# tornado-Backplane.net
KiCad netlist of a schematic drawn in EAGLE
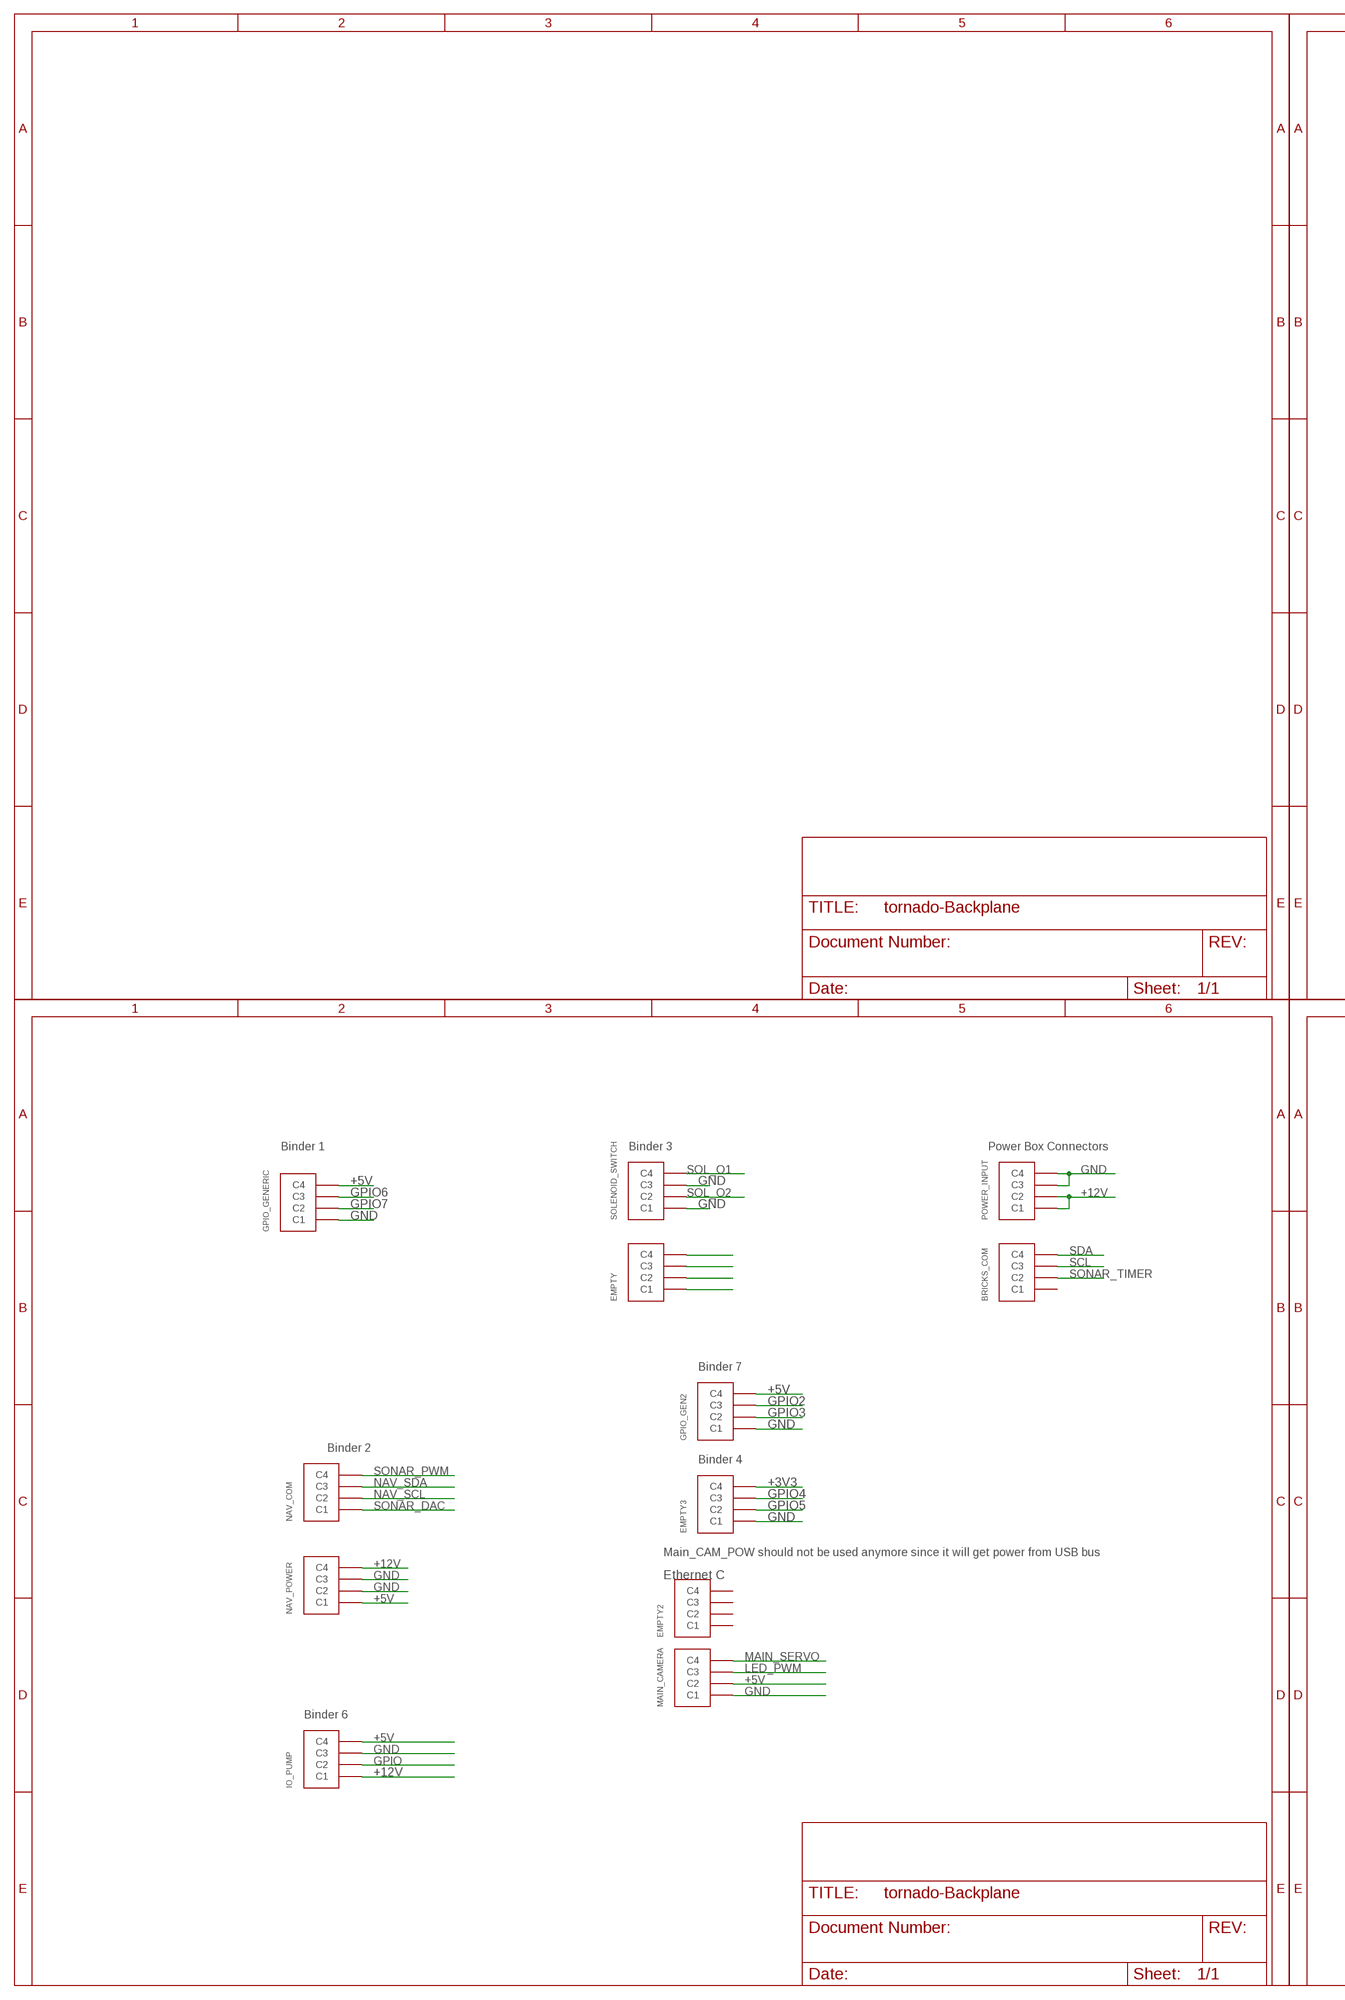
[diagram p0: schematic, sheet 1, part 1 of 2]
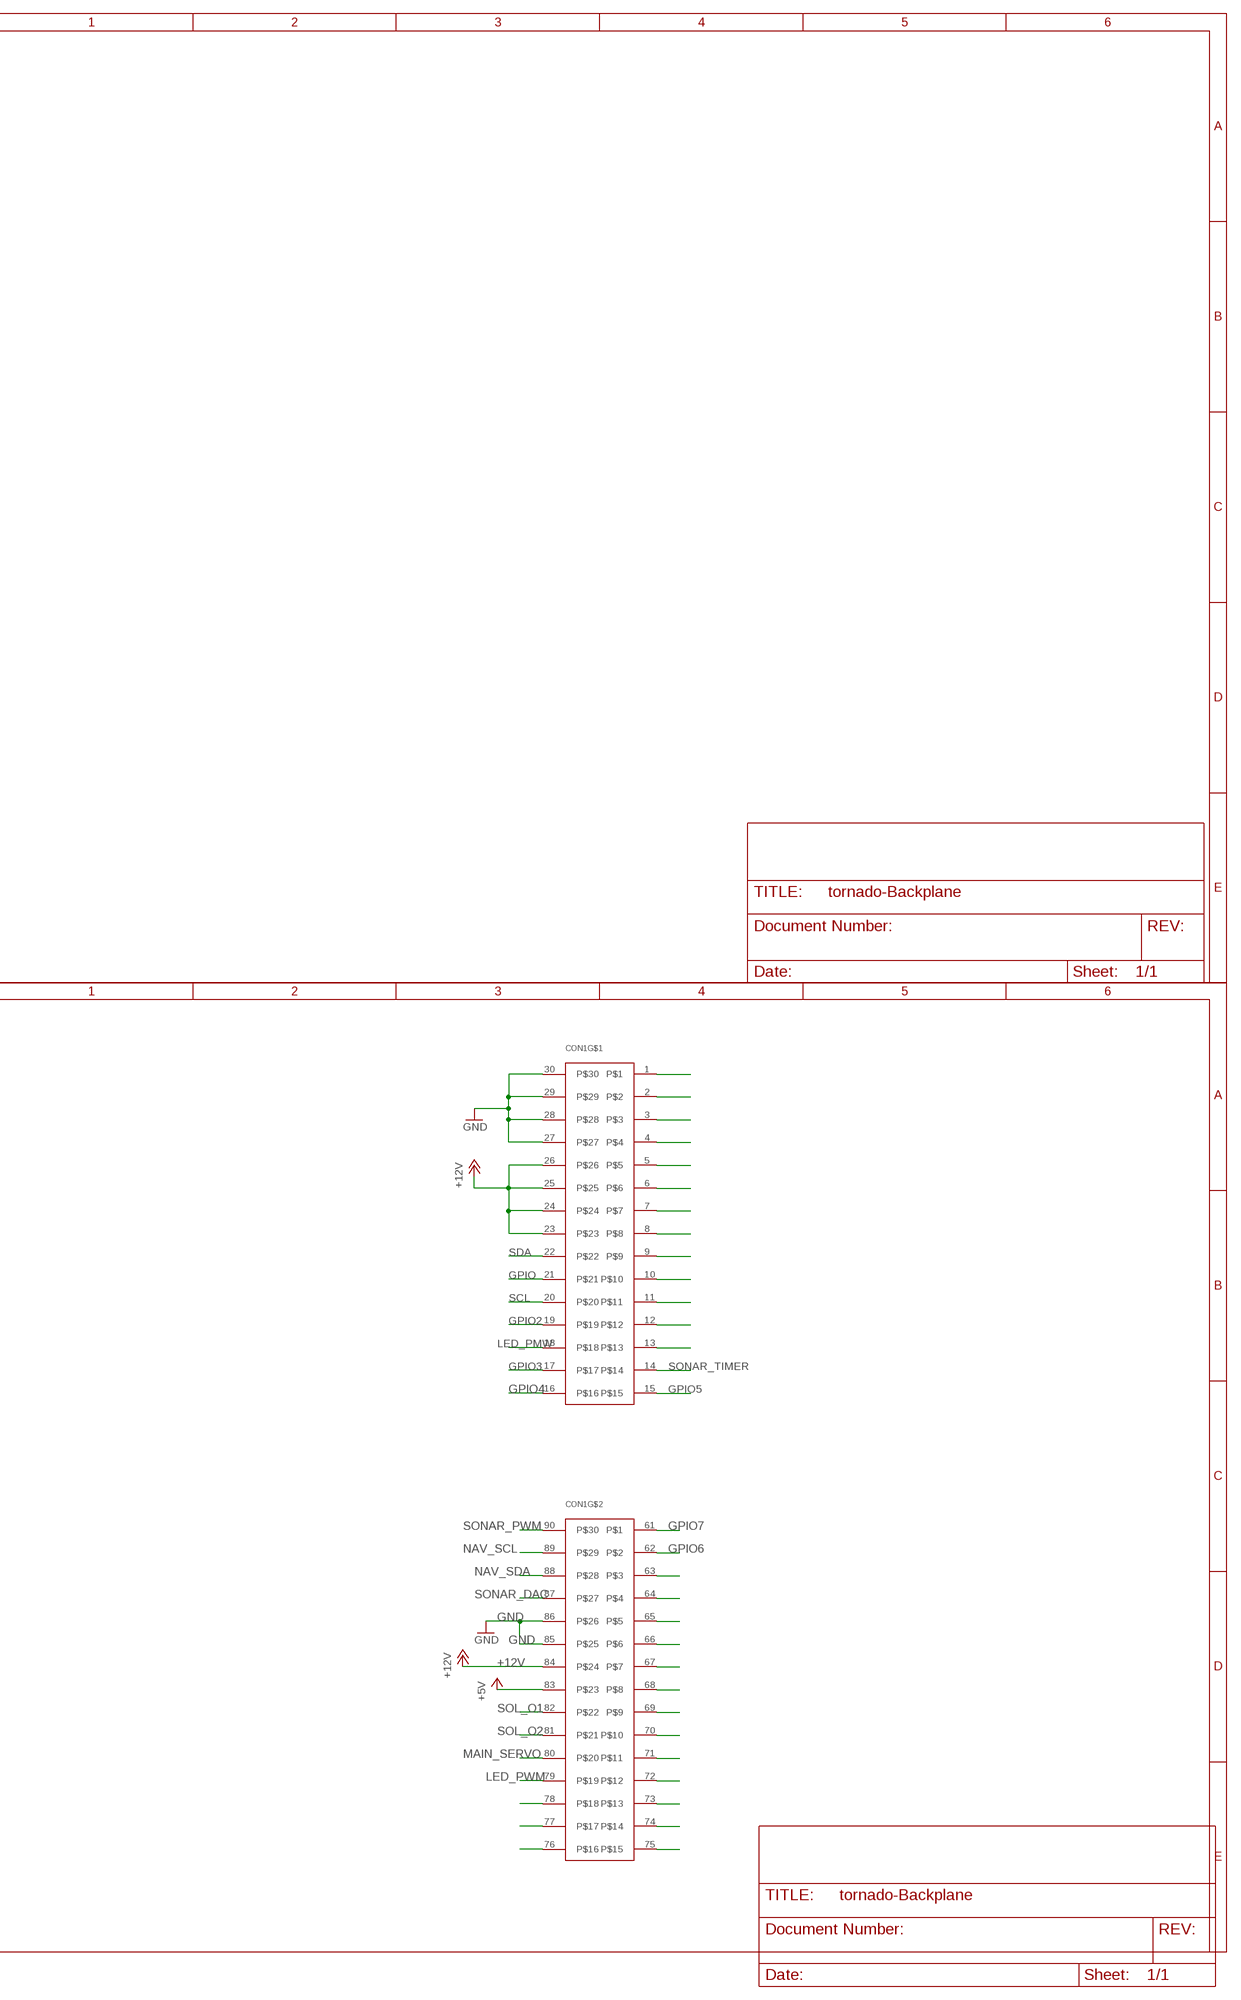
[diagram p1: schematic, sheet 1, part 2 of 2]

(export (version "E")
  (design (tool "Eeschema 10.0.6"))
  (components
    (comp (ref "BRICKS_COM")
      (value "MICRO-FIT-4-SMD-PART")
      (footprint "eagle-import:MICRO-FIT-4-SMD")
      (libsource (lib "eagle-import") (part "MICRO-FIT-4-SMD-PART"))
    )
    (comp (ref "CON1")
      (value "ROV_SHIELD_V2")
      (footprint "eagle-import:ROV_SHIELD_V2")
      (libsource (lib "eagle-import") (part "ROV_SHIELD_V2"))
    )
    (comp (ref "EMPTY")
      (value "MICRO-FIT-4-SMD-PART")
      (footprint "eagle-import:MICRO-FIT-4-SMD")
      (libsource (lib "eagle-import") (part "MICRO-FIT-4-SMD-PART"))
    )
    (comp (ref "EMPTY2")
      (value "MICRO-FIT-4-SMD-PART")
      (footprint "eagle-import:MICRO-FIT-4-SMD")
      (libsource (lib "eagle-import") (part "MICRO-FIT-4-SMD-PART"))
    )
    (comp (ref "EMPTY3")
      (value "MICRO-FIT-4-SMD-PART")
      (footprint "eagle-import:MICRO-FIT-4-SMD")
      (libsource (lib "eagle-import") (part "MICRO-FIT-4-SMD-PART"))
    )
    (comp (ref "GPIO_GEN2")
      (value "MICRO-FIT-4-SMD-PART")
      (footprint "eagle-import:MICRO-FIT-4-SMD")
      (libsource (lib "eagle-import") (part "MICRO-FIT-4-SMD-PART"))
    )
    (comp (ref "GPIO_GENERIC")
      (value "MICRO-FIT-4-SMD-PART")
      (footprint "eagle-import:MICRO-FIT-4-SMD")
      (libsource (lib "eagle-import") (part "MICRO-FIT-4-SMD-PART"))
    )
    (comp (ref "IO_PUMP")
      (value "MICRO-FIT-4-SMD-PART")
      (footprint "eagle-import:MICRO-FIT-4-SMD")
      (libsource (lib "eagle-import") (part "MICRO-FIT-4-SMD-PART"))
    )
    (comp (ref "MAIN_CAMERA")
      (value "MICRO-FIT-4-SMD-PART")
      (footprint "eagle-import:MICRO-FIT-4-SMD")
      (libsource (lib "eagle-import") (part "MICRO-FIT-4-SMD-PART"))
    )
    (comp (ref "NAV_COM")
      (value "MICRO-FIT-4-SMD-PART")
      (footprint "eagle-import:MICRO-FIT-4-SMD")
      (libsource (lib "eagle-import") (part "MICRO-FIT-4-SMD-PART"))
    )
    (comp (ref "NAV_POWER")
      (value "MICRO-FIT-4-SMD-PART")
      (footprint "eagle-import:MICRO-FIT-4-SMD")
      (libsource (lib "eagle-import") (part "MICRO-FIT-4-SMD-PART"))
    )
    (comp (ref "POWER_INPUT")
      (value "MICRO-FIT-4-SMD-PART")
      (footprint "eagle-import:MICRO-FIT-4-SMD")
      (libsource (lib "eagle-import") (part "MICRO-FIT-4-SMD-PART"))
    )
    (comp (ref "SOLENOID_SWITCH")
      (value "MICRO-FIT-4-SMD-PART")
      (footprint "eagle-import:MICRO-FIT-4-SMD")
      (libsource (lib "eagle-import") (part "MICRO-FIT-4-SMD-PART"))
    )
  )
  (nets
    (net (code "1") (name "+5V") (class "Default")
      (node (ref "CON1") (pin "83") (pinfunction "P$23_83") (pintype "bidirectional"))
      (node (ref "GPIO_GEN2") (pin "C4") (pinfunction "C4_C4") (pintype "bidirectional"))
      (node (ref "GPIO_GENERIC") (pin "C4") (pinfunction "C4_C4") (pintype "bidirectional"))
      (node (ref "IO_PUMP") (pin "C4") (pinfunction "C4_C4") (pintype "bidirectional"))
      (node (ref "MAIN_CAMERA") (pin "C2") (pinfunction "C2_C2") (pintype "bidirectional"))
      (node (ref "NAV_POWER") (pin "C1") (pinfunction "C1_C1") (pintype "bidirectional"))
    )
    (net (code "2") (name "+12V") (class "Default")
      (node (ref "CON1") (pin "23") (pinfunction "P$23_23") (pintype "bidirectional"))
      (node (ref "CON1") (pin "24") (pinfunction "P$24_24") (pintype "bidirectional"))
      (node (ref "CON1") (pin "25") (pinfunction "P$25_25") (pintype "bidirectional"))
      (node (ref "CON1") (pin "26") (pinfunction "P$26_26") (pintype "bidirectional"))
      (node (ref "CON1") (pin "84") (pinfunction "P$24_84") (pintype "bidirectional"))
      (node (ref "IO_PUMP") (pin "C1") (pinfunction "C1_C1") (pintype "bidirectional"))
      (node (ref "NAV_POWER") (pin "C4") (pinfunction "C4_C4") (pintype "bidirectional"))
      (node (ref "POWER_INPUT") (pin "C1") (pinfunction "C1_C1") (pintype "bidirectional"))
      (node (ref "POWER_INPUT") (pin "C2") (pinfunction "C2_C2") (pintype "bidirectional"))
    )
    (net (code "3") (name "/+3V3") (class "Default")
      (node (ref "EMPTY3") (pin "C4") (pinfunction "C4_C4") (pintype "bidirectional"))
    )
    (net (code "4") (name "/GPIO") (class "Default")
      (node (ref "CON1") (pin "21") (pinfunction "P$21_21") (pintype "bidirectional"))
      (node (ref "IO_PUMP") (pin "C2") (pinfunction "C2_C2") (pintype "bidirectional"))
    )
    (net (code "5") (name "/GPIO2") (class "Default")
      (node (ref "CON1") (pin "19") (pinfunction "P$19_19") (pintype "bidirectional"))
      (node (ref "GPIO_GEN2") (pin "C3") (pinfunction "C3_C3") (pintype "bidirectional"))
    )
    (net (code "6") (name "/GPIO3") (class "Default")
      (node (ref "CON1") (pin "17") (pinfunction "P$17_17") (pintype "bidirectional"))
      (node (ref "GPIO_GEN2") (pin "C2") (pinfunction "C2_C2") (pintype "bidirectional"))
    )
    (net (code "7") (name "/GPIO4") (class "Default")
      (node (ref "CON1") (pin "16") (pinfunction "P$16_16") (pintype "bidirectional"))
      (node (ref "EMPTY3") (pin "C3") (pinfunction "C3_C3") (pintype "bidirectional"))
    )
    (net (code "8") (name "/GPIO5") (class "Default")
      (node (ref "CON1") (pin "15") (pinfunction "P$15_15") (pintype "bidirectional"))
      (node (ref "EMPTY3") (pin "C2") (pinfunction "C2_C2") (pintype "bidirectional"))
    )
    (net (code "9") (name "/GPIO6") (class "Default")
      (node (ref "CON1") (pin "62") (pinfunction "P$2_62") (pintype "bidirectional"))
      (node (ref "GPIO_GENERIC") (pin "C3") (pinfunction "C3_C3") (pintype "bidirectional"))
    )
    (net (code "10") (name "/GPIO7") (class "Default")
      (node (ref "CON1") (pin "61") (pinfunction "P$1_61") (pintype "bidirectional"))
      (node (ref "GPIO_GENERIC") (pin "C2") (pinfunction "C2_C2") (pintype "bidirectional"))
    )
    (net (code "11") (name "/LED_PMW") (class "Default")
      (node (ref "CON1") (pin "18") (pinfunction "P$18_18") (pintype "bidirectional"))
    )
    (net (code "12") (name "/LED_PWM") (class "Default")
      (node (ref "CON1") (pin "79") (pinfunction "P$19_79") (pintype "bidirectional"))
      (node (ref "MAIN_CAMERA") (pin "C3") (pinfunction "C3_C3") (pintype "bidirectional"))
    )
    (net (code "13") (name "/MAIN_SERVO") (class "Default")
      (node (ref "CON1") (pin "80") (pinfunction "P$20_80") (pintype "bidirectional"))
      (node (ref "MAIN_CAMERA") (pin "C4") (pinfunction "C4_C4") (pintype "bidirectional"))
    )
    (net (code "14") (name "/NAV_SCL") (class "Default")
      (node (ref "CON1") (pin "89") (pinfunction "P$29_89") (pintype "bidirectional"))
      (node (ref "NAV_COM") (pin "C2") (pinfunction "C2_C2") (pintype "bidirectional"))
    )
    (net (code "15") (name "/NAV_SDA") (class "Default")
      (node (ref "CON1") (pin "88") (pinfunction "P$28_88") (pintype "bidirectional"))
      (node (ref "NAV_COM") (pin "C3") (pinfunction "C3_C3") (pintype "bidirectional"))
    )
    (net (code "16") (name "/SCL") (class "Default")
      (node (ref "BRICKS_COM") (pin "C3") (pinfunction "C3_C3") (pintype "bidirectional"))
      (node (ref "CON1") (pin "20") (pinfunction "P$20_20") (pintype "bidirectional"))
    )
    (net (code "17") (name "/SDA") (class "Default")
      (node (ref "BRICKS_COM") (pin "C4") (pinfunction "C4_C4") (pintype "bidirectional"))
      (node (ref "CON1") (pin "22") (pinfunction "P$22_22") (pintype "bidirectional"))
    )
    (net (code "18") (name "/SOL_O1") (class "Default")
      (node (ref "CON1") (pin "82") (pinfunction "P$22_82") (pintype "bidirectional"))
      (node (ref "SOLENOID_SWITCH") (pin "C4") (pinfunction "C4_C4") (pintype "bidirectional"))
    )
    (net (code "19") (name "/SOL_O2") (class "Default")
      (node (ref "CON1") (pin "81") (pinfunction "P$21_81") (pintype "bidirectional"))
      (node (ref "SOLENOID_SWITCH") (pin "C2") (pinfunction "C2_C2") (pintype "bidirectional"))
    )
    (net (code "20") (name "/SONAR_DAC") (class "Default")
      (node (ref "CON1") (pin "87") (pinfunction "P$27_87") (pintype "bidirectional"))
      (node (ref "NAV_COM") (pin "C1") (pinfunction "C1_C1") (pintype "bidirectional"))
    )
    (net (code "21") (name "/SONAR_PWM") (class "Default")
      (node (ref "CON1") (pin "90") (pinfunction "P$30_90") (pintype "bidirectional"))
      (node (ref "NAV_COM") (pin "C4") (pinfunction "C4_C4") (pintype "bidirectional"))
    )
    (net (code "22") (name "/SONAR_TIMER") (class "Default")
      (node (ref "BRICKS_COM") (pin "C2") (pinfunction "C2_C2") (pintype "bidirectional"))
      (node (ref "CON1") (pin "14") (pinfunction "P$14_14") (pintype "bidirectional"))
    )
    (net (code "23") (name "GND") (class "Default")
      (node (ref "CON1") (pin "27") (pinfunction "P$27_27") (pintype "bidirectional"))
      (node (ref "CON1") (pin "28") (pinfunction "P$28_28") (pintype "bidirectional"))
      (node (ref "CON1") (pin "29") (pinfunction "P$29_29") (pintype "bidirectional"))
      (node (ref "CON1") (pin "30") (pinfunction "P$30_30") (pintype "bidirectional"))
      (node (ref "CON1") (pin "85") (pinfunction "P$25_85") (pintype "bidirectional"))
      (node (ref "CON1") (pin "86") (pinfunction "P$26_86") (pintype "bidirectional"))
      (node (ref "EMPTY3") (pin "C1") (pinfunction "C1_C1") (pintype "bidirectional"))
      (node (ref "GPIO_GEN2") (pin "C1") (pinfunction "C1_C1") (pintype "bidirectional"))
      (node (ref "GPIO_GENERIC") (pin "C1") (pinfunction "C1_C1") (pintype "bidirectional"))
      (node (ref "IO_PUMP") (pin "C3") (pinfunction "C3_C3") (pintype "bidirectional"))
      (node (ref "MAIN_CAMERA") (pin "C1") (pinfunction "C1_C1") (pintype "bidirectional"))
      (node (ref "NAV_POWER") (pin "C2") (pinfunction "C2_C2") (pintype "bidirectional"))
      (node (ref "NAV_POWER") (pin "C3") (pinfunction "C3_C3") (pintype "bidirectional"))
      (node (ref "POWER_INPUT") (pin "C3") (pinfunction "C3_C3") (pintype "bidirectional"))
      (node (ref "POWER_INPUT") (pin "C4") (pinfunction "C4_C4") (pintype "bidirectional"))
      (node (ref "SOLENOID_SWITCH") (pin "C1") (pinfunction "C1_C1") (pintype "bidirectional"))
      (node (ref "SOLENOID_SWITCH") (pin "C3") (pinfunction "C3_C3") (pintype "bidirectional"))
    )
    (net (code "24") (name "unconnected-(BRICKS_COM-PadC1)") (class "Default")
      (node (ref "BRICKS_COM") (pin "C1") (pinfunction "C1_C1") (pintype "bidirectional"))
    )
    (net (code "25") (name "unconnected-(CON1A-P$1-Pad1)") (class "Default")
      (node (ref "CON1") (pin "1") (pinfunction "P$1_1") (pintype "bidirectional"))
    )
    (net (code "26") (name "unconnected-(CON1A-P$2-Pad2)") (class "Default")
      (node (ref "CON1") (pin "2") (pinfunction "P$2_2") (pintype "bidirectional"))
    )
    (net (code "27") (name "unconnected-(CON1A-P$3-Pad3)") (class "Default")
      (node (ref "CON1") (pin "3") (pinfunction "P$3_3") (pintype "bidirectional"))
    )
    (net (code "28") (name "unconnected-(CON1A-P$4-Pad4)") (class "Default")
      (node (ref "CON1") (pin "4") (pinfunction "P$4_4") (pintype "bidirectional"))
    )
    (net (code "29") (name "unconnected-(CON1A-P$5-Pad5)") (class "Default")
      (node (ref "CON1") (pin "5") (pinfunction "P$5_5") (pintype "bidirectional"))
    )
    (net (code "30") (name "unconnected-(CON1A-P$6-Pad6)") (class "Default")
      (node (ref "CON1") (pin "6") (pinfunction "P$6_6") (pintype "bidirectional"))
    )
    (net (code "31") (name "unconnected-(CON1A-P$7-Pad7)") (class "Default")
      (node (ref "CON1") (pin "7") (pinfunction "P$7_7") (pintype "bidirectional"))
    )
    (net (code "32") (name "unconnected-(CON1A-P$8-Pad8)") (class "Default")
      (node (ref "CON1") (pin "8") (pinfunction "P$8_8") (pintype "bidirectional"))
    )
    (net (code "33") (name "unconnected-(CON1A-P$9-Pad9)") (class "Default")
      (node (ref "CON1") (pin "9") (pinfunction "P$9_9") (pintype "bidirectional"))
    )
    (net (code "34") (name "unconnected-(CON1A-P$10-Pad10)") (class "Default")
      (node (ref "CON1") (pin "10") (pinfunction "P$10_10") (pintype "bidirectional"))
    )
    (net (code "35") (name "unconnected-(CON1A-P$11-Pad11)") (class "Default")
      (node (ref "CON1") (pin "11") (pinfunction "P$11_11") (pintype "bidirectional"))
    )
    (net (code "36") (name "unconnected-(CON1A-P$12-Pad12)") (class "Default")
      (node (ref "CON1") (pin "12") (pinfunction "P$12_12") (pintype "bidirectional"))
    )
    (net (code "37") (name "unconnected-(CON1A-P$13-Pad13)") (class "Default")
      (node (ref "CON1") (pin "13") (pinfunction "P$13_13") (pintype "bidirectional"))
    )
    (net (code "38") (name "unconnected-(CON1B-P$3-Pad63)") (class "Default")
      (node (ref "CON1") (pin "63") (pinfunction "P$3_63") (pintype "bidirectional"))
    )
    (net (code "39") (name "unconnected-(CON1B-P$4-Pad64)") (class "Default")
      (node (ref "CON1") (pin "64") (pinfunction "P$4_64") (pintype "bidirectional"))
    )
    (net (code "40") (name "unconnected-(CON1B-P$5-Pad65)") (class "Default")
      (node (ref "CON1") (pin "65") (pinfunction "P$5_65") (pintype "bidirectional"))
    )
    (net (code "41") (name "unconnected-(CON1B-P$6-Pad66)") (class "Default")
      (node (ref "CON1") (pin "66") (pinfunction "P$6_66") (pintype "bidirectional"))
    )
    (net (code "42") (name "unconnected-(CON1B-P$7-Pad67)") (class "Default")
      (node (ref "CON1") (pin "67") (pinfunction "P$7_67") (pintype "bidirectional"))
    )
    (net (code "43") (name "unconnected-(CON1B-P$8-Pad68)") (class "Default")
      (node (ref "CON1") (pin "68") (pinfunction "P$8_68") (pintype "bidirectional"))
    )
    (net (code "44") (name "unconnected-(CON1B-P$9-Pad69)") (class "Default")
      (node (ref "CON1") (pin "69") (pinfunction "P$9_69") (pintype "bidirectional"))
    )
    (net (code "45") (name "unconnected-(CON1B-P$10-Pad70)") (class "Default")
      (node (ref "CON1") (pin "70") (pinfunction "P$10_70") (pintype "bidirectional"))
    )
    (net (code "46") (name "unconnected-(CON1B-P$11-Pad71)") (class "Default")
      (node (ref "CON1") (pin "71") (pinfunction "P$11_71") (pintype "bidirectional"))
    )
    (net (code "47") (name "unconnected-(CON1B-P$12-Pad72)") (class "Default")
      (node (ref "CON1") (pin "72") (pinfunction "P$12_72") (pintype "bidirectional"))
    )
    (net (code "48") (name "unconnected-(CON1B-P$13-Pad73)") (class "Default")
      (node (ref "CON1") (pin "73") (pinfunction "P$13_73") (pintype "bidirectional"))
    )
    (net (code "49") (name "unconnected-(CON1B-P$14-Pad74)") (class "Default")
      (node (ref "CON1") (pin "74") (pinfunction "P$14_74") (pintype "bidirectional"))
    )
    (net (code "50") (name "unconnected-(CON1B-P$15-Pad75)") (class "Default")
      (node (ref "CON1") (pin "75") (pinfunction "P$15_75") (pintype "bidirectional"))
    )
    (net (code "51") (name "unconnected-(CON1B-P$16-Pad76)") (class "Default")
      (node (ref "CON1") (pin "76") (pinfunction "P$16_76") (pintype "bidirectional"))
    )
    (net (code "52") (name "unconnected-(CON1B-P$17-Pad77)") (class "Default")
      (node (ref "CON1") (pin "77") (pinfunction "P$17_77") (pintype "bidirectional"))
    )
    (net (code "53") (name "unconnected-(CON1B-P$18-Pad78)") (class "Default")
      (node (ref "CON1") (pin "78") (pinfunction "P$18_78") (pintype "bidirectional"))
    )
    (net (code "54") (name "unconnected-(EMPTY-PadC1)") (class "Default")
      (node (ref "EMPTY") (pin "C1") (pinfunction "C1_C1") (pintype "bidirectional"))
    )
    (net (code "55") (name "unconnected-(EMPTY-PadC2)") (class "Default")
      (node (ref "EMPTY") (pin "C2") (pinfunction "C2_C2") (pintype "bidirectional"))
    )
    (net (code "56") (name "unconnected-(EMPTY-PadC3)") (class "Default")
      (node (ref "EMPTY") (pin "C3") (pinfunction "C3_C3") (pintype "bidirectional"))
    )
    (net (code "57") (name "unconnected-(EMPTY-PadC4)") (class "Default")
      (node (ref "EMPTY") (pin "C4") (pinfunction "C4_C4") (pintype "bidirectional"))
    )
    (net (code "58") (name "unconnected-(EMPTY2-PadC1)") (class "Default")
      (node (ref "EMPTY2") (pin "C1") (pinfunction "C1_C1") (pintype "bidirectional"))
    )
    (net (code "59") (name "unconnected-(EMPTY2-PadC2)") (class "Default")
      (node (ref "EMPTY2") (pin "C2") (pinfunction "C2_C2") (pintype "bidirectional"))
    )
    (net (code "60") (name "unconnected-(EMPTY2-PadC3)") (class "Default")
      (node (ref "EMPTY2") (pin "C3") (pinfunction "C3_C3") (pintype "bidirectional"))
    )
    (net (code "61") (name "unconnected-(EMPTY2-PadC4)") (class "Default")
      (node (ref "EMPTY2") (pin "C4") (pinfunction "C4_C4") (pintype "bidirectional"))
    )
  )
)
